# FourRandomLamps_RevB.net
KiCad netlist of a schematic drawn in EAGLE
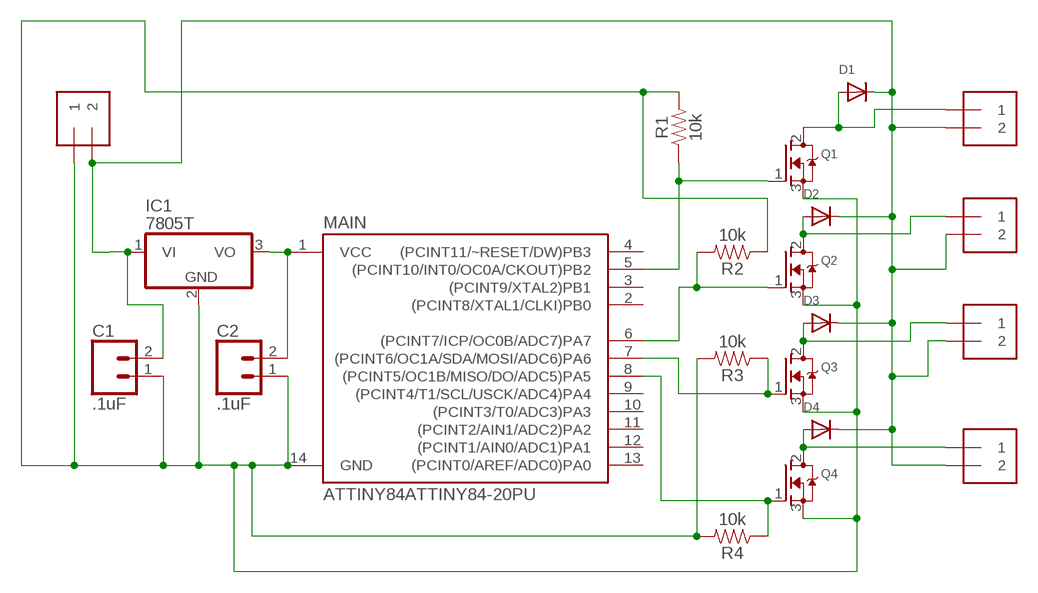
[diagram p0: schematic, sheet 1]

(export (version "E")
  (design (tool "Eeschema 10.0.6"))
  (components
    (comp (ref "12VDC")
      (value "1X2-3.5MM")
      (footprint "eagle-import:1X2-3.5MM")
      (libsource (lib "eagle-import") (part "1X2-3.5MM"))
    )
    (comp (ref "C1")
      (value ".1uF")
      (footprint "eagle-import:1X02_LOCK")
      (libsource (lib "eagle-import") (part "CONN_02LOCK"))
    )
    (comp (ref "C2")
      (value ".1uF")
      (footprint "eagle-import:1X02_LOCK")
      (libsource (lib "eagle-import") (part "CONN_02LOCK"))
    )
    (comp (ref "D1")
      (value "DIODEDO-1N4148")
      (footprint "eagle-import:DO-1N4148")
      (libsource (lib "eagle-import") (part "DIODEDO-1N4148"))
    )
    (comp (ref "D2")
      (value "DIODEDO-1N4148")
      (footprint "eagle-import:DO-1N4148")
      (libsource (lib "eagle-import") (part "DIODEDO-1N4148"))
    )
    (comp (ref "D3")
      (value "DIODEDO-1N4148")
      (footprint "eagle-import:DO-1N4148")
      (libsource (lib "eagle-import") (part "DIODEDO-1N4148"))
    )
    (comp (ref "D4")
      (value "DIODEDO-1N4148")
      (footprint "eagle-import:DO-1N4148")
      (libsource (lib "eagle-import") (part "DIODEDO-1N4148"))
    )
    (comp (ref "IC1")
      (value "7805T")
      (footprint "eagle-import:TO220H")
      (libsource (lib "eagle-import") (part "78T05"))
    )
    (comp (ref "LAMP1")
      (value "1X2-3.5MM")
      (footprint "eagle-import:1X2-3.5MM")
      (libsource (lib "eagle-import") (part "1X2-3.5MM"))
    )
    (comp (ref "LAMP2")
      (value "1X2-3.5MM")
      (footprint "eagle-import:1X2-3.5MM")
      (libsource (lib "eagle-import") (part "1X2-3.5MM"))
    )
    (comp (ref "LAMP3")
      (value "1X2-3.5MM")
      (footprint "eagle-import:1X2-3.5MM")
      (libsource (lib "eagle-import") (part "1X2-3.5MM"))
    )
    (comp (ref "LAMP4")
      (value "1X2-3.5MM")
      (footprint "eagle-import:1X2-3.5MM")
      (libsource (lib "eagle-import") (part "1X2-3.5MM"))
    )
    (comp (ref "MAIN")
      (value "ATTINY84ATTINY84-20PU")
      (footprint "eagle-import:DIP14")
      (libsource (lib "eagle-import") (part "ATTINY84ATTINY84-20PU"))
    )
    (comp (ref "Q1")
      (value "MOSFET-NGDS_TO220V")
      (footprint "eagle-import:TO220V")
      (libsource (lib "eagle-import") (part "MOSFET-NGDS_TO220V"))
    )
    (comp (ref "Q2")
      (value "MOSFET-NGDS_TO220V")
      (footprint "eagle-import:TO220V")
      (libsource (lib "eagle-import") (part "MOSFET-NGDS_TO220V"))
    )
    (comp (ref "Q3")
      (value "MOSFET-NGDS_TO220V")
      (footprint "eagle-import:TO220V")
      (libsource (lib "eagle-import") (part "MOSFET-NGDS_TO220V"))
    )
    (comp (ref "Q4")
      (value "MOSFET-NGDS_TO220V")
      (footprint "eagle-import:TO220V")
      (libsource (lib "eagle-import") (part "MOSFET-NGDS_TO220V"))
    )
    (comp (ref "R1")
      (value "10k")
      (footprint "eagle-import:AXIAL-0.3")
      (libsource (lib "eagle-import") (part "10KOHM-HORIZ-1/4W-5%"))
    )
    (comp (ref "R2")
      (value "10k")
      (footprint "eagle-import:AXIAL-0.3")
      (libsource (lib "eagle-import") (part "10KOHM-HORIZ-1/4W-5%"))
    )
    (comp (ref "R3")
      (value "10k")
      (footprint "eagle-import:AXIAL-0.3")
      (libsource (lib "eagle-import") (part "10KOHM-HORIZ-1/4W-5%"))
    )
    (comp (ref "R4")
      (value "10k")
      (footprint "eagle-import:AXIAL-0.3")
      (libsource (lib "eagle-import") (part "10KOHM-HORIZ-1/4W-5%"))
    )
  )
  (nets
    (net (code "1") (name "Net-(IC1-GND)") (class "Default")
      (node (ref "12VDC") (pin "1") (pinfunction "1_1") (pintype "passive"))
      (node (ref "C1") (pin "1") (pinfunction "1_1") (pintype "passive"))
      (node (ref "C2") (pin "1") (pinfunction "1_1") (pintype "passive"))
      (node (ref "IC1") (pin "2") (pinfunction "GND_2") (pintype "passive"))
      (node (ref "MAIN") (pin "14") (pinfunction "GND_14") (pintype "bidirectional"))
      (node (ref "Q1") (pin "3") (pinfunction "S_3") (pintype "bidirectional"))
      (node (ref "Q2") (pin "3") (pinfunction "S_3") (pintype "bidirectional"))
      (node (ref "Q3") (pin "3") (pinfunction "S_3") (pintype "bidirectional"))
      (node (ref "Q4") (pin "3") (pinfunction "S_3") (pintype "bidirectional"))
      (node (ref "R1") (pin "P$2") (pinfunction "2_P$2") (pintype "passive"))
      (node (ref "R2") (pin "P$1") (pinfunction "1_P$1") (pintype "passive"))
      (node (ref "R3") (pin "P$2") (pinfunction "2_P$2") (pintype "passive"))
      (node (ref "R4") (pin "P$2") (pinfunction "2_P$2") (pintype "passive"))
    )
    (net (code "2") (name "Net-(IC1-VI)") (class "Default")
      (node (ref "12VDC") (pin "2") (pinfunction "2_2") (pintype "passive"))
      (node (ref "C1") (pin "2") (pinfunction "2_2") (pintype "passive"))
      (node (ref "D1") (pin "C") (pinfunction "C_C") (pintype "passive"))
      (node (ref "D2") (pin "C") (pinfunction "C_C") (pintype "passive"))
      (node (ref "D3") (pin "C") (pinfunction "C_C") (pintype "passive"))
      (node (ref "D4") (pin "C") (pinfunction "C_C") (pintype "passive"))
      (node (ref "IC1") (pin "1") (pinfunction "VI_1") (pintype "input"))
      (node (ref "LAMP1") (pin "2") (pinfunction "2_2") (pintype "passive"))
      (node (ref "LAMP2") (pin "2") (pinfunction "2_2") (pintype "passive"))
      (node (ref "LAMP3") (pin "2") (pinfunction "2_2") (pintype "passive"))
      (node (ref "LAMP4") (pin "2") (pinfunction "2_2") (pintype "passive"))
    )
    (net (code "3") (name "Net-(IC1-VO)") (class "Default")
      (node (ref "C2") (pin "2") (pinfunction "2_2") (pintype "passive"))
      (node (ref "IC1") (pin "3") (pinfunction "VO_3") (pintype "passive"))
      (node (ref "MAIN") (pin "1") (pinfunction "VCC_1") (pintype "bidirectional"))
    )
    (net (code "4") (name "Net-(MAIN-(PCINT5{slash}OC1B{slash}MISO{slash}DO{slash}ADC5)PA5)") (class "Default")
      (node (ref "MAIN") (pin "8") (pinfunction "(PCINT5/OC1B/MISO/DO/ADC5)PA5_8") (pintype "bidirectional"))
      (node (ref "Q4") (pin "1") (pinfunction "G_1") (pintype "bidirectional"))
      (node (ref "R4") (pin "P$1") (pinfunction "1_P$1") (pintype "passive"))
    )
    (net (code "5") (name "Net-(MAIN-(PCINT6{slash}OC1A{slash}SDA{slash}MOSI{slash}ADC6)PA6)") (class "Default")
      (node (ref "MAIN") (pin "7") (pinfunction "(PCINT6/OC1A/SDA/MOSI/ADC6)PA6_7") (pintype "bidirectional"))
      (node (ref "Q3") (pin "1") (pinfunction "G_1") (pintype "bidirectional"))
      (node (ref "R3") (pin "P$1") (pinfunction "1_P$1") (pintype "passive"))
    )
    (net (code "6") (name "Net-(MAIN-(PCINT7{slash}ICP{slash}OC0B{slash}ADC7)PA7)") (class "Default")
      (node (ref "MAIN") (pin "6") (pinfunction "(PCINT7/ICP/OC0B/ADC7)PA7_6") (pintype "bidirectional"))
      (node (ref "Q2") (pin "1") (pinfunction "G_1") (pintype "bidirectional"))
      (node (ref "R2") (pin "P$2") (pinfunction "2_P$2") (pintype "passive"))
    )
    (net (code "7") (name "Net-(MAIN-(PCINT10{slash}INT0{slash}OC0A{slash}CKOUT)PB2)") (class "Default")
      (node (ref "MAIN") (pin "5") (pinfunction "(PCINT10/INT0/OC0A/CKOUT)PB2_5") (pintype "bidirectional"))
      (node (ref "Q1") (pin "1") (pinfunction "G_1") (pintype "bidirectional"))
      (node (ref "R1") (pin "P$1") (pinfunction "1_P$1") (pintype "passive"))
    )
    (net (code "8") (name "Net-(Q1-D)") (class "Default")
      (node (ref "D1") (pin "A") (pinfunction "A_A") (pintype "passive"))
      (node (ref "LAMP1") (pin "1") (pinfunction "1_1") (pintype "passive"))
      (node (ref "Q1") (pin "2") (pinfunction "D_2") (pintype "bidirectional"))
    )
    (net (code "9") (name "Net-(Q2-D)") (class "Default")
      (node (ref "D2") (pin "A") (pinfunction "A_A") (pintype "passive"))
      (node (ref "LAMP2") (pin "1") (pinfunction "1_1") (pintype "passive"))
      (node (ref "Q2") (pin "2") (pinfunction "D_2") (pintype "bidirectional"))
    )
    (net (code "10") (name "Net-(Q3-D)") (class "Default")
      (node (ref "D3") (pin "A") (pinfunction "A_A") (pintype "passive"))
      (node (ref "LAMP3") (pin "1") (pinfunction "1_1") (pintype "passive"))
      (node (ref "Q3") (pin "2") (pinfunction "D_2") (pintype "bidirectional"))
    )
    (net (code "11") (name "Net-(Q4-D)") (class "Default")
      (node (ref "D4") (pin "A") (pinfunction "A_A") (pintype "passive"))
      (node (ref "LAMP4") (pin "1") (pinfunction "1_1") (pintype "passive"))
      (node (ref "Q4") (pin "2") (pinfunction "D_2") (pintype "bidirectional"))
    )
    (net (code "12") (name "unconnected-(MAIN-(PCINT0{slash}AREF{slash}ADC0)PA0-Pad13)") (class "Default")
      (node (ref "MAIN") (pin "13") (pinfunction "(PCINT0/AREF/ADC0)PA0_13") (pintype "bidirectional"))
    )
    (net (code "13") (name "unconnected-(MAIN-(PCINT1{slash}AIN0{slash}ADC1)PA1-Pad12)") (class "Default")
      (node (ref "MAIN") (pin "12") (pinfunction "(PCINT1/AIN0/ADC1)PA1_12") (pintype "bidirectional"))
    )
    (net (code "14") (name "unconnected-(MAIN-(PCINT2{slash}AIN1{slash}ADC2)PA2-Pad11)") (class "Default")
      (node (ref "MAIN") (pin "11") (pinfunction "(PCINT2/AIN1/ADC2)PA2_11") (pintype "bidirectional"))
    )
    (net (code "15") (name "unconnected-(MAIN-(PCINT3{slash}T0{slash}ADC3)PA3-Pad10)") (class "Default")
      (node (ref "MAIN") (pin "10") (pinfunction "(PCINT3/T0/ADC3)PA3_10") (pintype "bidirectional"))
    )
    (net (code "16") (name "unconnected-(MAIN-(PCINT4{slash}T1{slash}SCL{slash}USCK{slash}ADC4)PA4-Pad9)") (class "Default")
      (node (ref "MAIN") (pin "9") (pinfunction "(PCINT4/T1/SCL/USCK/ADC4)PA4_9") (pintype "bidirectional"))
    )
    (net (code "17") (name "unconnected-(MAIN-(PCINT8{slash}XTAL1{slash}CLKI)PB0-Pad2)") (class "Default")
      (node (ref "MAIN") (pin "2") (pinfunction "(PCINT8/XTAL1/CLKI)PB0_2") (pintype "bidirectional"))
    )
    (net (code "18") (name "unconnected-(MAIN-(PCINT9{slash}XTAL2)PB1-Pad3)") (class "Default")
      (node (ref "MAIN") (pin "3") (pinfunction "(PCINT9/XTAL2)PB1_3") (pintype "bidirectional"))
    )
    (net (code "19") (name "unconnected-(MAIN-(PCINT11{slash}~{RESET{slash}DW})PB3-Pad4)") (class "Default")
      (node (ref "MAIN") (pin "4") (pinfunction "(PCINT11/~{RESET/DW})PB3_4") (pintype "bidirectional"))
    )
  )
)
